# Opto_Sheet.net
KiCad netlist of a schematic drawn in Altium Designer
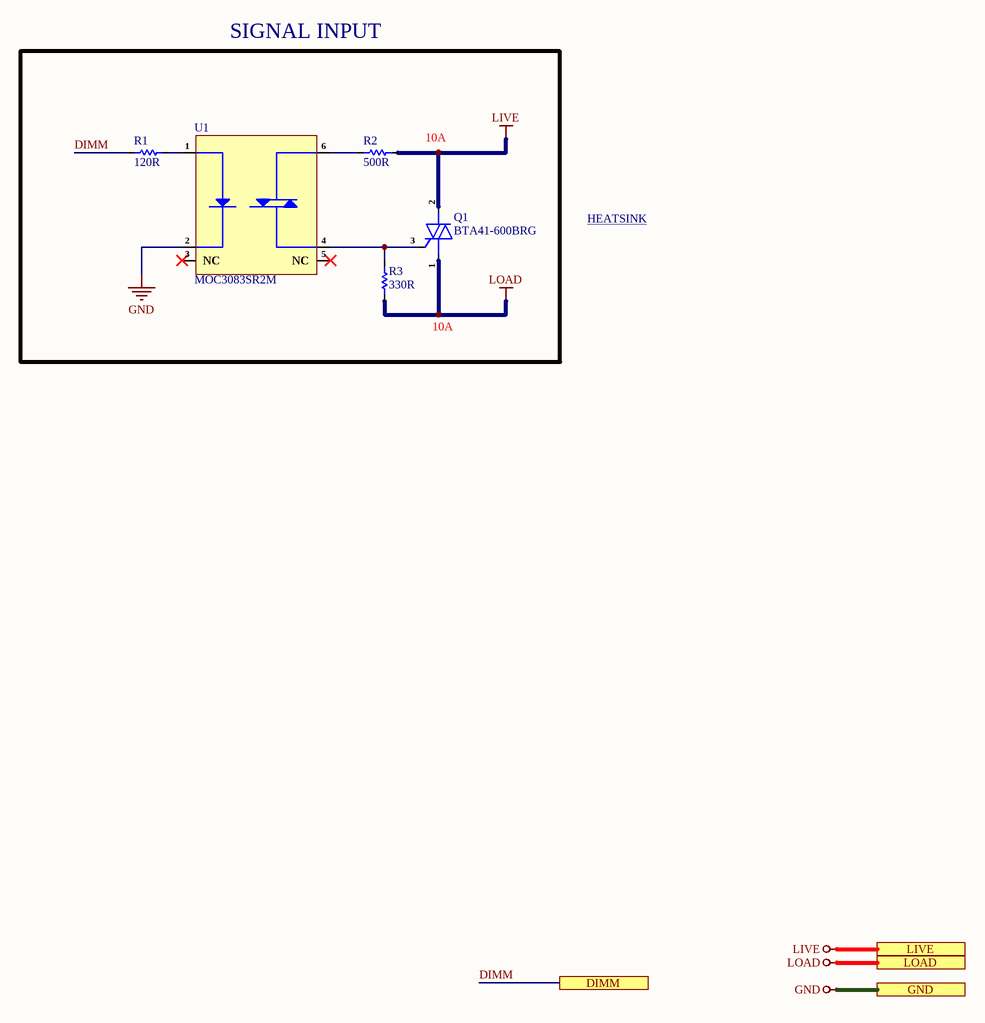
[diagram p0: Opto_Sheet.SchDoc]

(export (version "E")
  (design (tool "Eeschema 10.0.6"))
  (components
    (comp (ref "Q1")
      (value "BTA41-600BRG")
      (footprint "TO552P1530X450X2110-3B")
      (description "80mA 50mA 600V TOP-3 Thyristors (SCR)/Modules ROHS")
      (fields (field (name "MANUFACTURER") "STMicroelectronics") (field (name "LCSC PART NUMBER") "C9103"))
      (libsource (lib "SchLib") (part "BTA41-600BRG"))
    )
    (comp (ref "R1")
      (value "120R")
      (footprint "Res-0402")
      (description "RES 120 OHM 1% 1/16W 0402")
      (fields
        (field (name "MANUFACTURER") "Yageo")
        (field (name "MANUFACTURER PART NUMBER") "RC0402FR-07120RL")
      )
      (libsource (lib "eSpark Libraries") (part "RC0402FR-07120RL"))
    )
    (comp (ref "R2")
      (value "500R")
      (footprint "EWWR0006J500RT9")
      (description "Wirewound Resistors 500Ω 6W ±250ppm/℃ ±5% Plugin,D8xL23.5mm Through Hole Resistors ROHS")
      (fields
        (field (name "MANUFACTURER") "RESI")
        (field (name "MANUFACTURER PART NUMBER") "EWWR0006J500RT9")
      )
      (libsource (lib "SchLib") (part "EWWR0006J500RT9"))
    )
    (comp (ref "R3")
      (value "330R")
      (footprint "Res-1206")
      (description "500mW Thick Film Resistors 200V ±100ppm/℃ ±5% 330Ω 1206 Chip Resistor - Surface Mount ROHS")
      (fields
        (field (name "LCSC PART NUMBER") "C414913")
        (field (name "MANUFACTURER") "Royal Electronic Factory")
      )
      (libsource (lib "eSpark Libraries") (part "HP06W2J0331T5E"))
    )
    (comp (ref "U1")
      (value "MOC3083SR2M")
      (footprint "SMD-6P")
      (description "OPTOISOLATOR 4.17KV TRIAC 6SMD")
      (fields
        (field (name "LCSC PART NUMBER") "C111561")
        (field (name "MANUFACTURER") "ON Semiconductor / Fairchild")
      )
      (libsource (lib "eSpark Libraries") (part "MOC3083SR2M"))
    )
  )
  (nets
    (net (code "1") (name "/DIMM") (class "Default")
      (node (ref "R1") (pin "1") (pinfunction "1_1") (pintype "passive"))
    )
    (net (code "2") (name "GND") (class "Default")
      (node (ref "U1") (pin "2") (pinfunction "2_2") (pintype "passive"))
    )
    (net (code "3") (name "LIVE") (class "Default")
      (node (ref "Q1") (pin "2") (pinfunction "M2_2") (pintype "passive"))
      (node (ref "R2") (pin "2") (pinfunction "2_2") (pintype "passive"))
    )
    (net (code "4") (name "LOAD") (class "Default")
      (node (ref "Q1") (pin "1") (pinfunction "M1_1") (pintype "passive"))
      (node (ref "R3") (pin "1") (pinfunction "1_1") (pintype "passive"))
    )
    (net (code "5") (name "Net-(Q1-G)") (class "Default")
      (node (ref "Q1") (pin "3") (pinfunction "G_3") (pintype "passive"))
      (node (ref "R3") (pin "2") (pinfunction "2_2") (pintype "passive"))
      (node (ref "U1") (pin "4") (pinfunction "4_4") (pintype "passive"))
    )
    (net (code "6") (name "Net-(R1-Pad2)") (class "Default")
      (node (ref "R1") (pin "2") (pinfunction "2_2") (pintype "passive"))
      (node (ref "U1") (pin "1") (pinfunction "1_1") (pintype "passive"))
    )
    (net (code "7") (name "Net-(R2-Pad1)") (class "Default")
      (node (ref "R2") (pin "1") (pinfunction "1_1") (pintype "passive"))
      (node (ref "U1") (pin "6") (pinfunction "6_6") (pintype "passive"))
    )
    (net (code "8") (name "unconnected-(U1-NC-Pad3)") (class "Default")
      (node (ref "U1") (pin "3") (pinfunction "NC_3") (pintype "passive+no_connect"))
    )
    (net (code "9") (name "unconnected-(U1-NC-Pad5)") (class "Default")
      (node (ref "U1") (pin "5") (pinfunction "NC_5") (pintype "passive+no_connect"))
    )
  )
)
